# Encoder_Rev_3_pro_micro.net
KiCad netlist of a schematic drawn in EAGLE
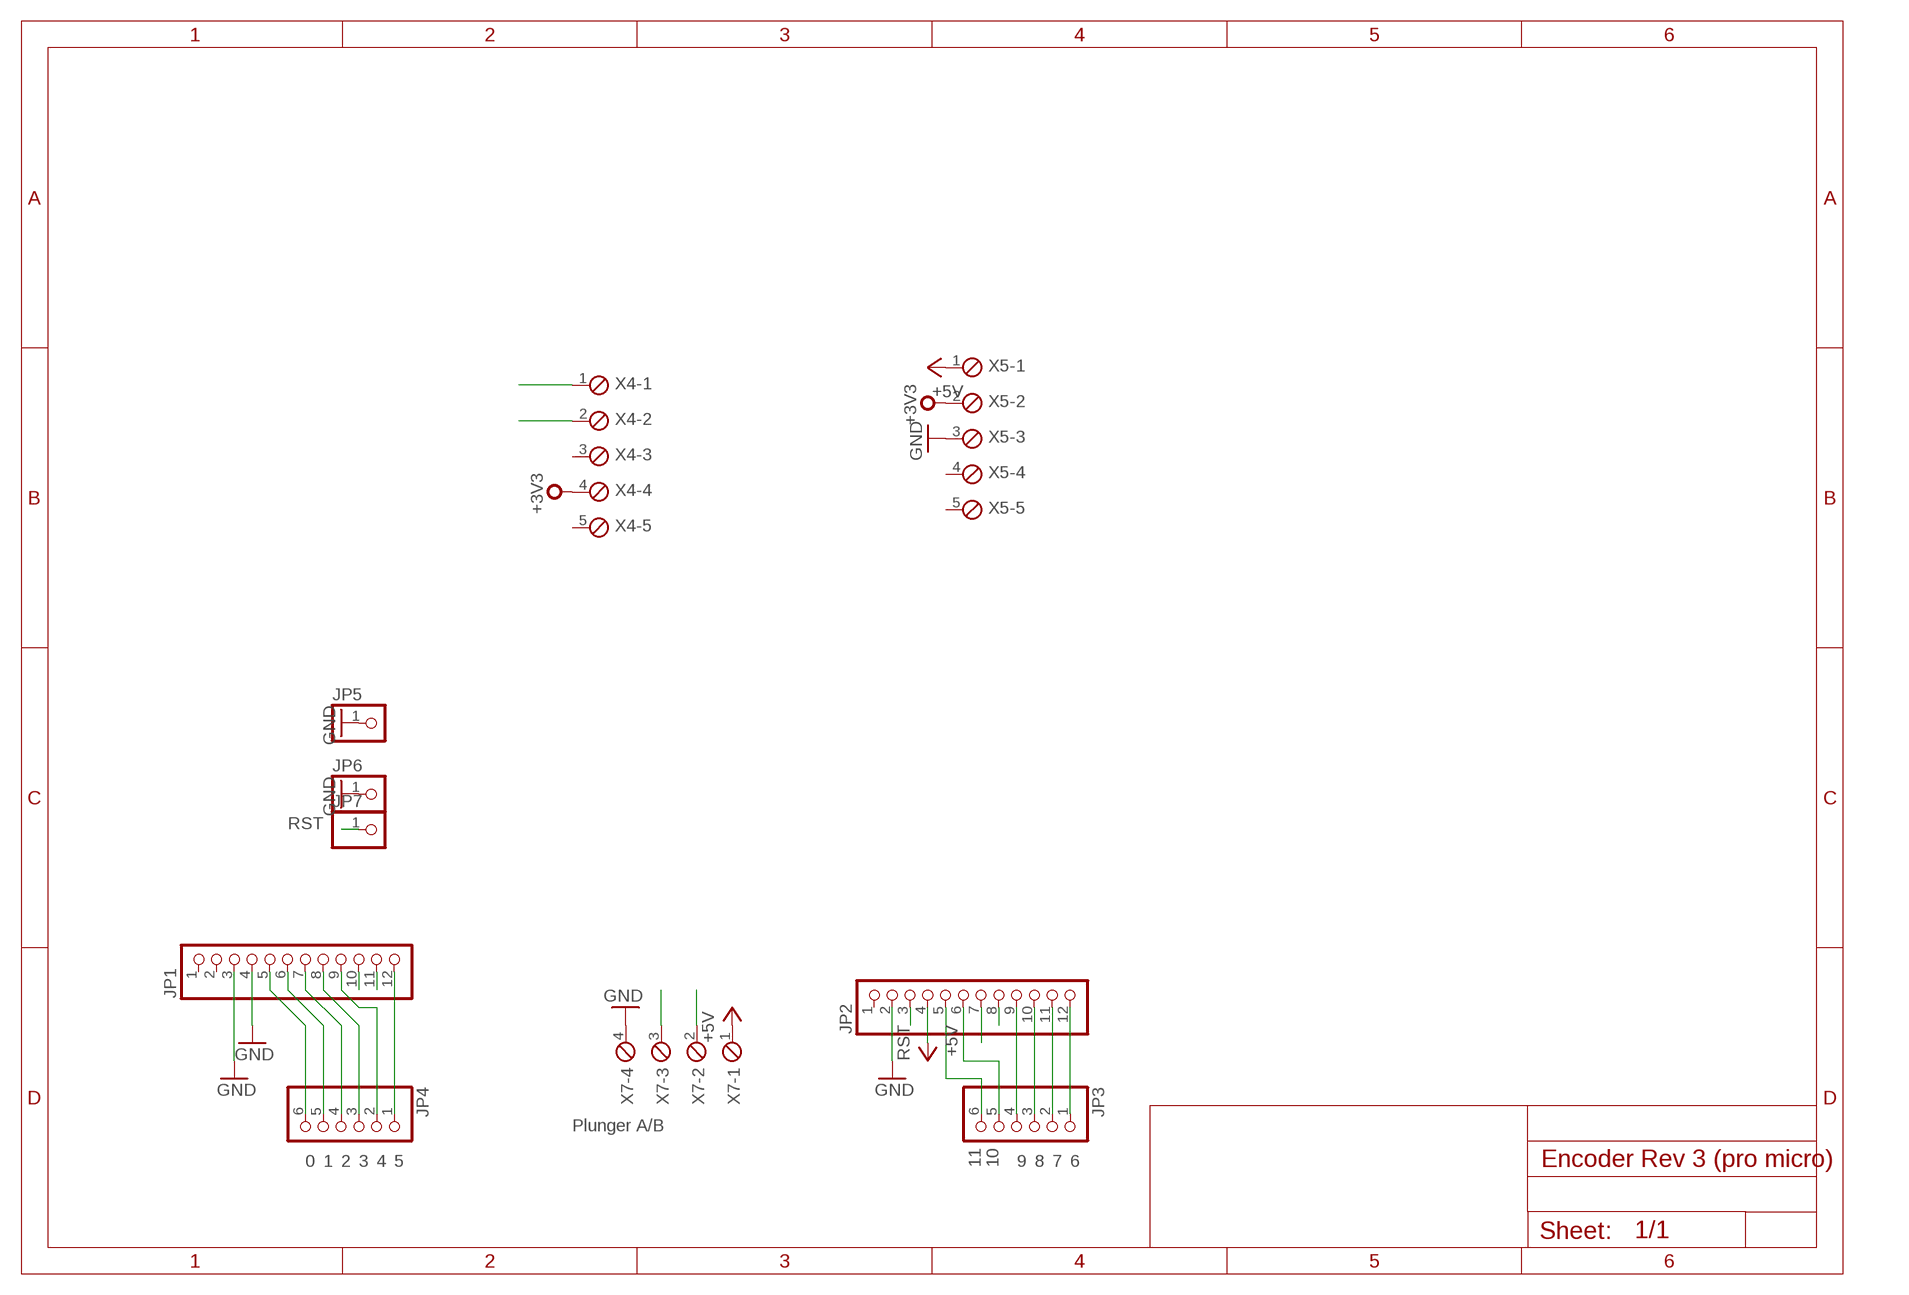
[diagram p0: schematic, sheet 1]

(export (version "E")
  (design (tool "Eeschema 10.0.6"))
  (components
    (comp (ref "JP1")
      (value "PINHD-1X12-CB")
      (footprint "eagle-import:1X12-CB")
      (libsource (lib "eagle-import") (part "PINHD-1X12-CB"))
    )
    (comp (ref "JP2")
      (value "PINHD-1X12-CB")
      (footprint "eagle-import:1X12-CB")
      (libsource (lib "eagle-import") (part "PINHD-1X12-CB"))
    )
    (comp (ref "JP3")
      (value "PINHD-1X6B")
      (footprint "eagle-import:1X06-BIG")
      (libsource (lib "eagle-import") (part "PINHD-1X6B"))
    )
    (comp (ref "JP4")
      (value "PINHD-1X6B")
      (footprint "eagle-import:1X06-BIG")
      (libsource (lib "eagle-import") (part "PINHD-1X6B"))
    )
    (comp (ref "JP5")
      (value "PINHD-1X1CB")
      (footprint "eagle-import:1X01-CLEANBIG")
      (libsource (lib "eagle-import") (part "PINHD-1X1CB"))
    )
    (comp (ref "JP6")
      (value "PINHD-1X1CB")
      (footprint "eagle-import:1X01-CLEANBIG")
      (libsource (lib "eagle-import") (part "PINHD-1X1CB"))
    )
    (comp (ref "JP7")
      (value "PINHD-1X1CB")
      (footprint "eagle-import:1X01-CLEANBIG")
      (libsource (lib "eagle-import") (part "PINHD-1X1CB"))
    )
    (comp (ref "X4")
      (value "MPT5")
      (footprint "eagle-import:5POL254")
      (libsource (lib "eagle-import") (part "MPT5"))
    )
    (comp (ref "X5")
      (value "MPT5")
      (footprint "eagle-import:5POL254")
      (libsource (lib "eagle-import") (part "MPT5"))
    )
    (comp (ref "X7")
      (value "MPT4")
      (footprint "eagle-import:4POL254")
      (libsource (lib "eagle-import") (part "MPT4"))
    )
  )
  (nets
    (net (code "1") (name "+3V3") (class "Default")
      (node (ref "X4") (pin "4") (pinfunction "1_4") (pintype "passive"))
      (node (ref "X5") (pin "2") (pinfunction "1_2") (pintype "passive"))
    )
    (net (code "2") (name "+5V") (class "Default")
      (node (ref "JP2") (pin "4") (pinfunction "4_4") (pintype "passive"))
      (node (ref "X5") (pin "1") (pinfunction "1_1") (pintype "passive"))
      (node (ref "X7") (pin "1") (pinfunction "1_1") (pintype "passive"))
    )
    (net (code "3") (name "/A") (class "Default")
      (node (ref "JP1") (pin "10") (pinfunction "10_10") (pintype "passive"))
      (node (ref "X7") (pin "3") (pinfunction "1_3") (pintype "passive"))
    )
    (net (code "4") (name "/B") (class "Default")
      (node (ref "JP1") (pin "11") (pinfunction "11_11") (pintype "passive"))
      (node (ref "X7") (pin "2") (pinfunction "1_2") (pintype "passive"))
    )
    (net (code "5") (name "/RST") (class "Default")
      (node (ref "JP2") (pin "3") (pinfunction "3_3") (pintype "passive"))
      (node (ref "JP7") (pin "1") (pinfunction "1_1") (pintype "passive"))
    )
    (net (code "6") (name "/XOUT") (class "Default")
      (node (ref "JP2") (pin "8") (pinfunction "8_8") (pintype "passive"))
      (node (ref "X4") (pin "1") (pinfunction "1_1") (pintype "passive"))
    )
    (net (code "7") (name "/YOUT") (class "Default")
      (node (ref "JP2") (pin "7") (pinfunction "7_7") (pintype "passive"))
      (node (ref "X4") (pin "2") (pinfunction "1_2") (pintype "passive"))
    )
    (net (code "8") (name "GND") (class "Default")
      (node (ref "JP1") (pin "3") (pinfunction "3_3") (pintype "passive"))
      (node (ref "JP1") (pin "4") (pinfunction "4_4") (pintype "passive"))
      (node (ref "JP2") (pin "2") (pinfunction "2_2") (pintype "passive"))
      (node (ref "JP5") (pin "1") (pinfunction "1_1") (pintype "passive"))
      (node (ref "JP6") (pin "1") (pinfunction "1_1") (pintype "passive"))
      (node (ref "X5") (pin "3") (pinfunction "1_3") (pintype "passive"))
      (node (ref "X7") (pin "4") (pinfunction "1_4") (pintype "passive"))
    )
    (net (code "9") (name "Net-(JP1-Pad5)") (class "Default")
      (node (ref "JP1") (pin "5") (pinfunction "5_5") (pintype "passive"))
      (node (ref "JP4") (pin "6") (pinfunction "6_6") (pintype "passive"))
    )
    (net (code "10") (name "Net-(JP1-Pad6)") (class "Default")
      (node (ref "JP1") (pin "6") (pinfunction "6_6") (pintype "passive"))
      (node (ref "JP4") (pin "5") (pinfunction "5_5") (pintype "passive"))
    )
    (net (code "11") (name "Net-(JP1-Pad7)") (class "Default")
      (node (ref "JP1") (pin "7") (pinfunction "7_7") (pintype "passive"))
      (node (ref "JP4") (pin "4") (pinfunction "4_4") (pintype "passive"))
    )
    (net (code "12") (name "Net-(JP1-Pad8)") (class "Default")
      (node (ref "JP1") (pin "8") (pinfunction "8_8") (pintype "passive"))
      (node (ref "JP4") (pin "3") (pinfunction "3_3") (pintype "passive"))
    )
    (net (code "13") (name "Net-(JP1-Pad9)") (class "Default")
      (node (ref "JP1") (pin "9") (pinfunction "9_9") (pintype "passive"))
      (node (ref "JP4") (pin "2") (pinfunction "2_2") (pintype "passive"))
    )
    (net (code "14") (name "Net-(JP1-Pad12)") (class "Default")
      (node (ref "JP1") (pin "12") (pinfunction "12_12") (pintype "passive"))
      (node (ref "JP4") (pin "1") (pinfunction "1_1") (pintype "passive"))
    )
    (net (code "15") (name "Net-(JP2-Pad5)") (class "Default")
      (node (ref "JP2") (pin "5") (pinfunction "5_5") (pintype "passive"))
      (node (ref "JP3") (pin "6") (pinfunction "6_6") (pintype "passive"))
    )
    (net (code "16") (name "Net-(JP2-Pad6)") (class "Default")
      (node (ref "JP2") (pin "6") (pinfunction "6_6") (pintype "passive"))
      (node (ref "JP3") (pin "5") (pinfunction "5_5") (pintype "passive"))
    )
    (net (code "17") (name "Net-(JP2-Pad9)") (class "Default")
      (node (ref "JP2") (pin "9") (pinfunction "9_9") (pintype "passive"))
      (node (ref "JP3") (pin "4") (pinfunction "4_4") (pintype "passive"))
    )
    (net (code "18") (name "Net-(JP2-Pad10)") (class "Default")
      (node (ref "JP2") (pin "10") (pinfunction "10_10") (pintype "passive"))
      (node (ref "JP3") (pin "3") (pinfunction "3_3") (pintype "passive"))
    )
    (net (code "19") (name "Net-(JP2-Pad11)") (class "Default")
      (node (ref "JP2") (pin "11") (pinfunction "11_11") (pintype "passive"))
      (node (ref "JP3") (pin "2") (pinfunction "2_2") (pintype "passive"))
    )
    (net (code "20") (name "Net-(JP2-Pad12)") (class "Default")
      (node (ref "JP2") (pin "12") (pinfunction "12_12") (pintype "passive"))
      (node (ref "JP3") (pin "1") (pinfunction "1_1") (pintype "passive"))
    )
    (net (code "21") (name "unconnected-(JP1-Pad1)") (class "Default")
      (node (ref "JP1") (pin "1") (pinfunction "1_1") (pintype "passive"))
    )
    (net (code "22") (name "unconnected-(JP1-Pad2)") (class "Default")
      (node (ref "JP1") (pin "2") (pinfunction "2_2") (pintype "passive"))
    )
    (net (code "23") (name "unconnected-(JP2-Pad1)") (class "Default")
      (node (ref "JP2") (pin "1") (pinfunction "1_1") (pintype "passive"))
    )
    (net (code "24") (name "unconnected-(X4C-1-Pad3)") (class "Default")
      (node (ref "X4") (pin "3") (pinfunction "1_3") (pintype "passive"))
    )
    (net (code "25") (name "unconnected-(X4E-1-Pad5)") (class "Default")
      (node (ref "X4") (pin "5") (pinfunction "1_5") (pintype "passive"))
    )
    (net (code "26") (name "unconnected-(X5D-1-Pad4)") (class "Default")
      (node (ref "X5") (pin "4") (pinfunction "1_4") (pintype "passive"))
    )
    (net (code "27") (name "unconnected-(X5E-1-Pad5)") (class "Default")
      (node (ref "X5") (pin "5") (pinfunction "1_5") (pintype "passive"))
    )
  )
)
